# APM32F103RCT6.net
KiCad netlist of a schematic drawn in Altium Designer
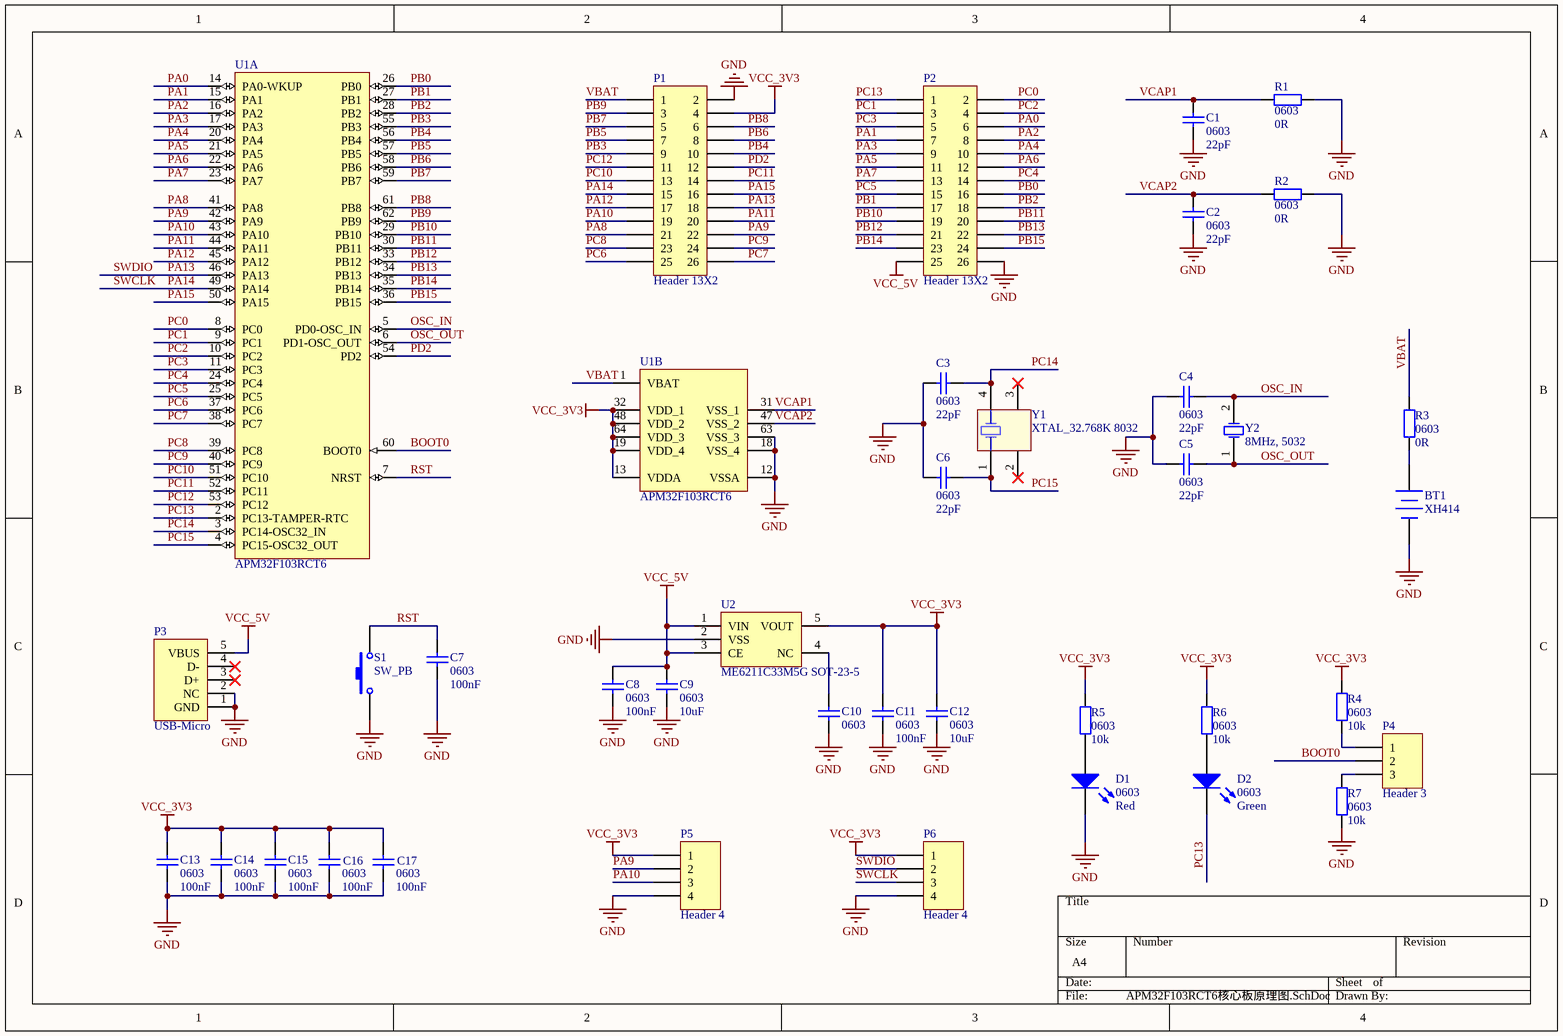
[diagram p0: APM32F103RCT6核心板原理图.SchDoc]

(export (version "E")
  (design (tool "Eeschema 10.0.6"))
  (components
    (comp (ref "BT1")
      (value "XH414")
      (footprint "XH414")
      (description "Multicell Battery")
      (fields (field (name "PUBLISHER") "Altium Limited"))
      (libsource (lib "Miscellaneous Devices") (part "Battery"))
    )
    (comp (ref "C1")
      (value "22pF")
      (footprint "0603")
      (description "Capacitor 0603")
      (fields (field (name "Comment") "Cap 0603"))
      (libsource (lib "Schlib1") (part "Cap 0603"))
    )
    (comp (ref "C2")
      (value "22pF")
      (footprint "0603")
      (description "Capacitor 0603")
      (fields (field (name "Comment") "Cap 0603"))
      (libsource (lib "Schlib1") (part "Cap 0603"))
    )
    (comp (ref "C3")
      (value "22pF")
      (footprint "0603")
      (description "Capacitor 0603")
      (fields (field (name "Comment") "Cap 0603"))
      (libsource (lib "Schlib1") (part "Cap 0603"))
    )
    (comp (ref "C4")
      (value "22pF")
      (footprint "0603")
      (description "Capacitor 0603")
      (fields (field (name "Comment") "Cap 0603"))
      (libsource (lib "Schlib1") (part "Cap 0603"))
    )
    (comp (ref "C5")
      (value "22pF")
      (footprint "0603")
      (description "Capacitor 0603")
      (fields (field (name "Comment") "Cap 0603"))
      (libsource (lib "Schlib1") (part "Cap 0603"))
    )
    (comp (ref "C6")
      (value "22pF")
      (footprint "0603")
      (description "Capacitor 0603")
      (fields (field (name "Comment") "Cap 0603"))
      (libsource (lib "Schlib1") (part "Cap 0603"))
    )
    (comp (ref "C7")
      (value "100nF")
      (footprint "0603")
      (description "Capacitor 0603")
      (fields (field (name "Comment") "Cap 0603"))
      (libsource (lib "Schlib1") (part "Cap 0603"))
    )
    (comp (ref "C8")
      (value "100nF")
      (footprint "0603")
      (description "Capacitor 0603")
      (fields (field (name "Comment") "Cap 0603"))
      (libsource (lib "Schlib1") (part "Cap 0603"))
    )
    (comp (ref "C9")
      (value "10uF")
      (footprint "0603")
      (description "Capacitor 0603")
      (fields (field (name "Comment") "Cap 0603"))
      (libsource (lib "Schlib1") (part "Cap 0603"))
    )
    (comp (ref "C10")
      (value "Cap 0603")
      (footprint "0603")
      (description "Capacitor 0603")
      (libsource (lib "Schlib1") (part "Cap 0603"))
    )
    (comp (ref "C11")
      (value "100nF")
      (footprint "0603")
      (description "Capacitor 0603")
      (fields (field (name "Comment") "Cap 0603"))
      (libsource (lib "Schlib1") (part "Cap 0603"))
    )
    (comp (ref "C12")
      (value "10uF")
      (footprint "0603")
      (description "Capacitor 0603")
      (fields (field (name "Comment") "Cap 0603"))
      (libsource (lib "Schlib1") (part "Cap 0603"))
    )
    (comp (ref "C13")
      (value "100nF")
      (footprint "0603")
      (description "Capacitor 0603")
      (fields (field (name "Comment") "Cap 0603"))
      (libsource (lib "Schlib1") (part "Cap 0603"))
    )
    (comp (ref "C14")
      (value "100nF")
      (footprint "0603")
      (description "Capacitor 0603")
      (fields (field (name "Comment") "Cap 0603"))
      (libsource (lib "Schlib1") (part "Cap 0603"))
    )
    (comp (ref "C15")
      (value "100nF")
      (footprint "0603")
      (description "Capacitor 0603")
      (fields (field (name "Comment") "Cap 0603"))
      (libsource (lib "Schlib1") (part "Cap 0603"))
    )
    (comp (ref "C16")
      (value "100nF")
      (footprint "0603")
      (description "Capacitor 0603")
      (fields (field (name "Comment") "Cap 0603"))
      (libsource (lib "Schlib1") (part "Cap 0603"))
    )
    (comp (ref "C17")
      (value "100nF")
      (footprint "0603")
      (description "Capacitor 0603")
      (fields (field (name "Comment") "Cap 0603"))
      (libsource (lib "Schlib1") (part "Cap 0603"))
    )
    (comp (ref "D1")
      (value "Red")
      (footprint "0603")
      (description "LED 0603")
      (libsource (lib "Schlib1") (part "LED 0603"))
    )
    (comp (ref "D2")
      (value "Green")
      (footprint "0603")
      (description "LED 0603")
      (libsource (lib "Schlib1") (part "LED 0603"))
    )
    (comp (ref "P1")
      (value "Header 13X2")
      (footprint "HDR2X13")
      (description "Header, 13-Pin, Dual row")
      (fields (field (name "PUBLISHER") "Altium Limited"))
      (libsource (lib "Miscellaneous Connectors") (part "Header 13X2"))
    )
    (comp (ref "P2")
      (value "Header 13X2")
      (footprint "HDR2X13")
      (description "Header, 13-Pin, Dual row")
      (fields (field (name "PUBLISHER") "Altium Limited"))
      (libsource (lib "Miscellaneous Connectors") (part "Header 13X2"))
    )
    (comp (ref "P3")
      (value "USB-Micro")
      (footprint "USB Micro")
      (libsource (lib "Schlib1") (part "USB-Micro"))
    )
    (comp (ref "P4")
      (value "Header 3")
      (footprint "HDR1X3")
      (description "Header, 3-Pin")
      (fields (field (name "PUBLISHER") "Altium Limited"))
      (libsource (lib "Miscellaneous Connectors") (part "Header 3"))
    )
    (comp (ref "P5")
      (value "Header 4")
      (footprint "HDR1X4")
      (description "Header, 4-Pin")
      (fields (field (name "PUBLISHER") "Altium Limited"))
      (libsource (lib "Miscellaneous Connectors") (part "Header 4"))
    )
    (comp (ref "P6")
      (value "Header 4")
      (footprint "HDR1X4")
      (description "Header, 4-Pin")
      (fields (field (name "PUBLISHER") "Altium Limited"))
      (libsource (lib "Miscellaneous Connectors") (part "Header 4"))
    )
    (comp (ref "R1")
      (value "0R")
      (footprint "0603")
      (description "Resistor 0603")
      (fields (field (name "Comment") "Res 0603"))
      (libsource (lib "Schlib1") (part "Res 0603"))
    )
    (comp (ref "R2")
      (value "0R")
      (footprint "0603")
      (description "Resistor 0603")
      (fields (field (name "Comment") "Res 0603"))
      (libsource (lib "Schlib1") (part "Res 0603"))
    )
    (comp (ref "R3")
      (value "0R")
      (footprint "0603")
      (description "Resistor 0603")
      (fields (field (name "Comment") "Res 0603"))
      (libsource (lib "") (part "Res 0603_1"))
    )
    (comp (ref "R4")
      (value "10k")
      (footprint "0603")
      (description "Resistor 0603")
      (fields (field (name "Comment") "Res 0603"))
      (libsource (lib "") (part "Res 0603_2"))
    )
    (comp (ref "R5")
      (value "10k")
      (footprint "0603")
      (description "Resistor 0603")
      (fields (field (name "Comment") "Res 0603"))
      (libsource (lib "") (part "Res 0603_1"))
    )
    (comp (ref "R6")
      (value "10k")
      (footprint "0603")
      (description "Resistor 0603")
      (fields (field (name "Comment") "Res 0603"))
      (libsource (lib "") (part "Res 0603_1"))
    )
    (comp (ref "R7")
      (value "10k")
      (footprint "0603")
      (description "Resistor 0603")
      (fields (field (name "Comment") "Res 0603"))
      (libsource (lib "") (part "Res 0603_2"))
    )
    (comp (ref "S1") (value "SW_PB") (footprint "SW-2Pin") (libsource (lib "Schlib1") (part "SW_PB")))
    (comp (ref "U1")
      (value "APM32F103RCT6")
      (footprint "STM-LQFP64_M")
      (fields (field (name "PARTNUMBER") "STM32F103RCT6"))
      (libsource (lib "STMicroelectronics STM32 F1") (part "STM32F103RCT6"))
    )
    (comp (ref "U2")
      (value "ME6211C33M5G SOT-23-5")
      (footprint "SOT-23-5")
      (libsource (lib "Schlib1") (part "ME6211C33M5G"))
    )
    (comp (ref "Y1")
      (value "XTAL_32.768K 8032")
      (footprint "XTAL_8032")
      (libsource (lib "Schlib1") (part "XTAL_32.768K 8032"))
    )
    (comp (ref "Y2")
      (value "8MHz, 5032")
      (footprint "XTAL 5032")
      (description "Crystal Oscillator")
      (fields (field (name "PUBLISHER") "Altium Limited"))
      (libsource (lib "Schlib1") (part "XTAL"))
    )
  )
  (nets
    (net (code "1") (name "/BOOT0") (class "Default")
      (node (ref "P4") (pin "2") (pinfunction "2_2") (pintype "passive"))
      (node (ref "U1") (pin "60") (pinfunction "BOOT0_60") (pintype "input"))
    )
    (net (code "2") (name "/OSC_IN") (class "Default")
      (node (ref "C4") (pin "1") (pinfunction "1_1") (pintype "passive"))
      (node (ref "U1") (pin "5") (pinfunction "PD0-OSC_IN_5") (pintype "bidirectional"))
      (node (ref "Y2") (pin "2") (pinfunction "OSC2_2") (pintype "passive"))
    )
    (net (code "3") (name "/OSC_OUT") (class "Default")
      (node (ref "C5") (pin "1") (pinfunction "1_1") (pintype "passive"))
      (node (ref "U1") (pin "6") (pinfunction "PD1-OSC_OUT_6") (pintype "bidirectional"))
      (node (ref "Y2") (pin "1") (pinfunction "OSC1_1") (pintype "passive"))
    )
    (net (code "4") (name "/PA0") (class "Default")
      (node (ref "P2") (pin "6") (pinfunction "6_6") (pintype "passive"))
      (node (ref "U1") (pin "14") (pinfunction "PA0-WKUP_14") (pintype "bidirectional"))
    )
    (net (code "5") (name "/PA1") (class "Default")
      (node (ref "P2") (pin "7") (pinfunction "7_7") (pintype "passive"))
      (node (ref "U1") (pin "15") (pinfunction "PA1_15") (pintype "bidirectional"))
    )
    (net (code "6") (name "/PA2") (class "Default")
      (node (ref "P2") (pin "8") (pinfunction "8_8") (pintype "passive"))
      (node (ref "U1") (pin "16") (pinfunction "PA2_16") (pintype "bidirectional"))
    )
    (net (code "7") (name "/PA3") (class "Default")
      (node (ref "P2") (pin "9") (pinfunction "9_9") (pintype "passive"))
      (node (ref "U1") (pin "17") (pinfunction "PA3_17") (pintype "bidirectional"))
    )
    (net (code "8") (name "/PA4") (class "Default")
      (node (ref "P2") (pin "10") (pinfunction "10_10") (pintype "passive"))
      (node (ref "U1") (pin "20") (pinfunction "PA4_20") (pintype "bidirectional"))
    )
    (net (code "9") (name "/PA5") (class "Default")
      (node (ref "P2") (pin "11") (pinfunction "11_11") (pintype "passive"))
      (node (ref "U1") (pin "21") (pinfunction "PA5_21") (pintype "bidirectional"))
    )
    (net (code "10") (name "/PA6") (class "Default")
      (node (ref "P2") (pin "12") (pinfunction "12_12") (pintype "passive"))
      (node (ref "U1") (pin "22") (pinfunction "PA6_22") (pintype "bidirectional"))
    )
    (net (code "11") (name "/PA7") (class "Default")
      (node (ref "P2") (pin "13") (pinfunction "13_13") (pintype "passive"))
      (node (ref "U1") (pin "23") (pinfunction "PA7_23") (pintype "bidirectional"))
    )
    (net (code "12") (name "/PA8") (class "Default")
      (node (ref "P1") (pin "21") (pinfunction "21_21") (pintype "passive"))
      (node (ref "U1") (pin "41") (pinfunction "PA8_41") (pintype "bidirectional"))
    )
    (net (code "13") (name "/PA9") (class "Default")
      (node (ref "P1") (pin "22") (pinfunction "22_22") (pintype "passive"))
      (node (ref "P5") (pin "2") (pinfunction "2_2") (pintype "passive"))
      (node (ref "U1") (pin "42") (pinfunction "PA9_42") (pintype "bidirectional"))
    )
    (net (code "14") (name "/PA10") (class "Default")
      (node (ref "P1") (pin "19") (pinfunction "19_19") (pintype "passive"))
      (node (ref "P5") (pin "3") (pinfunction "3_3") (pintype "passive"))
      (node (ref "U1") (pin "43") (pinfunction "PA10_43") (pintype "bidirectional"))
    )
    (net (code "15") (name "/PA11") (class "Default")
      (node (ref "P1") (pin "20") (pinfunction "20_20") (pintype "passive"))
      (node (ref "U1") (pin "44") (pinfunction "PA11_44") (pintype "bidirectional"))
    )
    (net (code "16") (name "/PA12") (class "Default")
      (node (ref "P1") (pin "17") (pinfunction "17_17") (pintype "passive"))
      (node (ref "U1") (pin "45") (pinfunction "PA12_45") (pintype "bidirectional"))
    )
    (net (code "17") (name "/PA13") (class "Default")
      (node (ref "P1") (pin "18") (pinfunction "18_18") (pintype "passive"))
      (node (ref "P6") (pin "2") (pinfunction "2_2") (pintype "passive"))
      (node (ref "U1") (pin "46") (pinfunction "PA13_46") (pintype "bidirectional"))
    )
    (net (code "18") (name "/PA14") (class "Default")
      (node (ref "P1") (pin "15") (pinfunction "15_15") (pintype "passive"))
      (node (ref "P6") (pin "3") (pinfunction "3_3") (pintype "passive"))
      (node (ref "U1") (pin "49") (pinfunction "PA14_49") (pintype "bidirectional"))
    )
    (net (code "19") (name "/PA15") (class "Default")
      (node (ref "P1") (pin "16") (pinfunction "16_16") (pintype "passive"))
      (node (ref "U1") (pin "50") (pinfunction "PA15_50") (pintype "bidirectional"))
    )
    (net (code "20") (name "/PB0") (class "Default")
      (node (ref "P2") (pin "16") (pinfunction "16_16") (pintype "passive"))
      (node (ref "U1") (pin "26") (pinfunction "PB0_26") (pintype "bidirectional"))
    )
    (net (code "21") (name "/PB1") (class "Default")
      (node (ref "P2") (pin "17") (pinfunction "17_17") (pintype "passive"))
      (node (ref "U1") (pin "27") (pinfunction "PB1_27") (pintype "bidirectional"))
    )
    (net (code "22") (name "/PB2") (class "Default")
      (node (ref "P2") (pin "18") (pinfunction "18_18") (pintype "passive"))
      (node (ref "U1") (pin "28") (pinfunction "PB2_28") (pintype "bidirectional"))
    )
    (net (code "23") (name "/PB3") (class "Default")
      (node (ref "P1") (pin "9") (pinfunction "9_9") (pintype "passive"))
      (node (ref "U1") (pin "55") (pinfunction "PB3_55") (pintype "bidirectional"))
    )
    (net (code "24") (name "/PB4") (class "Default")
      (node (ref "P1") (pin "10") (pinfunction "10_10") (pintype "passive"))
      (node (ref "U1") (pin "56") (pinfunction "PB4_56") (pintype "bidirectional"))
    )
    (net (code "25") (name "/PB5") (class "Default")
      (node (ref "P1") (pin "7") (pinfunction "7_7") (pintype "passive"))
      (node (ref "U1") (pin "57") (pinfunction "PB5_57") (pintype "bidirectional"))
    )
    (net (code "26") (name "/PB6") (class "Default")
      (node (ref "P1") (pin "8") (pinfunction "8_8") (pintype "passive"))
      (node (ref "U1") (pin "58") (pinfunction "PB6_58") (pintype "bidirectional"))
    )
    (net (code "27") (name "/PB7") (class "Default")
      (node (ref "P1") (pin "5") (pinfunction "5_5") (pintype "passive"))
      (node (ref "U1") (pin "59") (pinfunction "PB7_59") (pintype "bidirectional"))
    )
    (net (code "28") (name "/PB8") (class "Default")
      (node (ref "P1") (pin "6") (pinfunction "6_6") (pintype "passive"))
      (node (ref "U1") (pin "61") (pinfunction "PB8_61") (pintype "bidirectional"))
    )
    (net (code "29") (name "/PB9") (class "Default")
      (node (ref "P1") (pin "3") (pinfunction "3_3") (pintype "passive"))
      (node (ref "U1") (pin "62") (pinfunction "PB9_62") (pintype "bidirectional"))
    )
    (net (code "30") (name "/PB10") (class "Default")
      (node (ref "P2") (pin "19") (pinfunction "19_19") (pintype "passive"))
      (node (ref "U1") (pin "29") (pinfunction "PB10_29") (pintype "bidirectional"))
    )
    (net (code "31") (name "/PB11") (class "Default")
      (node (ref "P2") (pin "20") (pinfunction "20_20") (pintype "passive"))
      (node (ref "U1") (pin "30") (pinfunction "PB11_30") (pintype "bidirectional"))
    )
    (net (code "32") (name "/PB12") (class "Default")
      (node (ref "P2") (pin "21") (pinfunction "21_21") (pintype "passive"))
      (node (ref "U1") (pin "33") (pinfunction "PB12_33") (pintype "bidirectional"))
    )
    (net (code "33") (name "/PB13") (class "Default")
      (node (ref "P2") (pin "22") (pinfunction "22_22") (pintype "passive"))
      (node (ref "U1") (pin "34") (pinfunction "PB13_34") (pintype "bidirectional"))
    )
    (net (code "34") (name "/PB14") (class "Default")
      (node (ref "P2") (pin "23") (pinfunction "23_23") (pintype "passive"))
      (node (ref "U1") (pin "35") (pinfunction "PB14_35") (pintype "bidirectional"))
    )
    (net (code "35") (name "/PB15") (class "Default")
      (node (ref "P2") (pin "24") (pinfunction "24_24") (pintype "passive"))
      (node (ref "U1") (pin "36") (pinfunction "PB15_36") (pintype "bidirectional"))
    )
    (net (code "36") (name "/PC0") (class "Default")
      (node (ref "P2") (pin "2") (pinfunction "2_2") (pintype "passive"))
      (node (ref "U1") (pin "8") (pinfunction "PC0_8") (pintype "bidirectional"))
    )
    (net (code "37") (name "/PC1") (class "Default")
      (node (ref "P2") (pin "3") (pinfunction "3_3") (pintype "passive"))
      (node (ref "U1") (pin "9") (pinfunction "PC1_9") (pintype "bidirectional"))
    )
    (net (code "38") (name "/PC2") (class "Default")
      (node (ref "P2") (pin "4") (pinfunction "4_4") (pintype "passive"))
      (node (ref "U1") (pin "10") (pinfunction "PC2_10") (pintype "bidirectional"))
    )
    (net (code "39") (name "/PC3") (class "Default")
      (node (ref "P2") (pin "5") (pinfunction "5_5") (pintype "passive"))
      (node (ref "U1") (pin "11") (pinfunction "PC3_11") (pintype "bidirectional"))
    )
    (net (code "40") (name "/PC4") (class "Default")
      (node (ref "P2") (pin "14") (pinfunction "14_14") (pintype "passive"))
      (node (ref "U1") (pin "24") (pinfunction "PC4_24") (pintype "bidirectional"))
    )
    (net (code "41") (name "/PC5") (class "Default")
      (node (ref "P2") (pin "15") (pinfunction "15_15") (pintype "passive"))
      (node (ref "U1") (pin "25") (pinfunction "PC5_25") (pintype "bidirectional"))
    )
    (net (code "42") (name "/PC6") (class "Default")
      (node (ref "P1") (pin "25") (pinfunction "25_25") (pintype "passive"))
      (node (ref "U1") (pin "37") (pinfunction "PC6_37") (pintype "bidirectional"))
    )
    (net (code "43") (name "/PC7") (class "Default")
      (node (ref "P1") (pin "26") (pinfunction "26_26") (pintype "passive"))
      (node (ref "U1") (pin "38") (pinfunction "PC7_38") (pintype "bidirectional"))
    )
    (net (code "44") (name "/PC8") (class "Default")
      (node (ref "P1") (pin "23") (pinfunction "23_23") (pintype "passive"))
      (node (ref "U1") (pin "39") (pinfunction "PC8_39") (pintype "bidirectional"))
    )
    (net (code "45") (name "/PC9") (class "Default")
      (node (ref "P1") (pin "24") (pinfunction "24_24") (pintype "passive"))
      (node (ref "U1") (pin "40") (pinfunction "PC9_40") (pintype "bidirectional"))
    )
    (net (code "46") (name "/PC10") (class "Default")
      (node (ref "P1") (pin "13") (pinfunction "13_13") (pintype "passive"))
      (node (ref "U1") (pin "51") (pinfunction "PC10_51") (pintype "bidirectional"))
    )
    (net (code "47") (name "/PC11") (class "Default")
      (node (ref "P1") (pin "14") (pinfunction "14_14") (pintype "passive"))
      (node (ref "U1") (pin "52") (pinfunction "PC11_52") (pintype "bidirectional"))
    )
    (net (code "48") (name "/PC12") (class "Default")
      (node (ref "P1") (pin "11") (pinfunction "11_11") (pintype "passive"))
      (node (ref "U1") (pin "53") (pinfunction "PC12_53") (pintype "bidirectional"))
    )
    (net (code "49") (name "/PC13") (class "Default")
      (node (ref "D2") (pin "2") (pinfunction "K_2") (pintype "passive"))
      (node (ref "P2") (pin "1") (pinfunction "1_1") (pintype "passive"))
      (node (ref "U1") (pin "2") (pinfunction "PC13-TAMPER-RTC_2") (pintype "bidirectional"))
    )
    (net (code "50") (name "/PC14") (class "Default")
      (node (ref "C3") (pin "1") (pinfunction "1_1") (pintype "passive"))
      (node (ref "U1") (pin "3") (pinfunction "PC14-OSC32_IN_3") (pintype "bidirectional"))
      (node (ref "Y1") (pin "4") (pinfunction "OSC2_4") (pintype "passive"))
    )
    (net (code "51") (name "/PC15") (class "Default")
      (node (ref "C6") (pin "1") (pinfunction "1_1") (pintype "passive"))
      (node (ref "U1") (pin "4") (pinfunction "PC15-OSC32_OUT_4") (pintype "bidirectional"))
      (node (ref "Y1") (pin "1") (pinfunction "OSC1_1") (pintype "passive"))
    )
    (net (code "52") (name "/PD2") (class "Default")
      (node (ref "P1") (pin "12") (pinfunction "12_12") (pintype "passive"))
      (node (ref "U1") (pin "54") (pinfunction "PD2_54") (pintype "bidirectional"))
    )
    (net (code "53") (name "/RST") (class "Default")
      (node (ref "C7") (pin "2") (pinfunction "2_2") (pintype "passive"))
      (node (ref "S1") (pin "2") (pinfunction "2_2") (pintype "passive"))
      (node (ref "U1") (pin "7") (pinfunction "NRST_7") (pintype "bidirectional"))
    )
    (net (code "54") (name "/VBAT") (class "Default")
      (node (ref "P1") (pin "1") (pinfunction "1_1") (pintype "passive"))
      (node (ref "R3") (pin "1") (pinfunction "1_1") (pintype "passive"))
      (node (ref "U1") (pin "1") (pinfunction "VBAT_1") (pintype "power_in"))
    )
    (net (code "55") (name "/VCAP1") (class "Default")
      (node (ref "C1") (pin "1") (pinfunction "1_1") (pintype "passive"))
      (node (ref "R1") (pin "1") (pinfunction "1_1") (pintype "passive"))
      (node (ref "U1") (pin "31") (pinfunction "VSS_1_31") (pintype "power_in"))
    )
    (net (code "56") (name "/VCAP2") (class "Default")
      (node (ref "C2") (pin "1") (pinfunction "1_1") (pintype "passive"))
      (node (ref "R2") (pin "1") (pinfunction "1_1") (pintype "passive"))
      (node (ref "U1") (pin "47") (pinfunction "VSS_2_47") (pintype "power_in"))
    )
    (net (code "57") (name "GND") (class "Default")
      (node (ref "BT1") (pin "2") (pinfunction "-_2") (pintype "passive"))
      (node (ref "C1") (pin "2") (pinfunction "2_2") (pintype "passive"))
      (node (ref "C10") (pin "1") (pinfunction "1_1") (pintype "passive"))
      (node (ref "C11") (pin "1") (pinfunction "1_1") (pintype "passive"))
      (node (ref "C12") (pin "1") (pinfunction "1_1") (pintype "passive"))
      (node (ref "C13") (pin "1") (pinfunction "1_1") (pintype "passive"))
      (node (ref "C14") (pin "1") (pinfunction "1_1") (pintype "passive"))
      (node (ref "C15") (pin "1") (pinfunction "1_1") (pintype "passive"))
      (node (ref "C16") (pin "1") (pinfunction "1_1") (pintype "passive"))
      (node (ref "C17") (pin "1") (pinfunction "1_1") (pintype "passive"))
      (node (ref "C2") (pin "2") (pinfunction "2_2") (pintype "passive"))
      (node (ref "C3") (pin "2") (pinfunction "2_2") (pintype "passive"))
      (node (ref "C4") (pin "2") (pinfunction "2_2") (pintype "passive"))
      (node (ref "C5") (pin "2") (pinfunction "2_2") (pintype "passive"))
      (node (ref "C6") (pin "2") (pinfunction "2_2") (pintype "passive"))
      (node (ref "C7") (pin "1") (pinfunction "1_1") (pintype "passive"))
      (node (ref "C8") (pin "1") (pinfunction "1_1") (pintype "passive"))
      (node (ref "C9") (pin "1") (pinfunction "1_1") (pintype "passive"))
      (node (ref "D1") (pin "2") (pinfunction "K_2") (pintype "passive"))
      (node (ref "P1") (pin "2") (pinfunction "2_2") (pintype "passive"))
      (node (ref "P2") (pin "26") (pinfunction "26_26") (pintype "passive"))
      (node (ref "P3") (pin "1") (pinfunction "GND_1") (pintype "power_in"))
      (node (ref "P3") (pin "2") (pinfunction "NC_2") (pintype "power_in"))
      (node (ref "P5") (pin "4") (pinfunction "4_4") (pintype "passive"))
      (node (ref "P6") (pin "4") (pinfunction "4_4") (pintype "passive"))
      (node (ref "R1") (pin "2") (pinfunction "2_2") (pintype "passive"))
      (node (ref "R2") (pin "2") (pinfunction "2_2") (pintype "passive"))
      (node (ref "R7") (pin "1") (pinfunction "1_1") (pintype "passive"))
      (node (ref "S1") (pin "1") (pinfunction "1_1") (pintype "passive"))
      (node (ref "U1") (pin "12") (pinfunction "VSSA_12") (pintype "power_in"))
      (node (ref "U1") (pin "18") (pinfunction "VSS_4_18") (pintype "power_in"))
      (node (ref "U1") (pin "63") (pinfunction "VSS_3_63") (pintype "power_in"))
      (node (ref "U2") (pin "2") (pinfunction "VSS_2") (pintype "power_in"))
    )
    (net (code "58") (name "Net-(BT1-+)") (class "Default")
      (node (ref "BT1") (pin "1") (pinfunction "+_1") (pintype "passive"))
      (node (ref "R3") (pin "2") (pinfunction "2_2") (pintype "passive"))
    )
    (net (code "59") (name "Net-(D1-A)") (class "Default")
      (node (ref "D1") (pin "1") (pinfunction "A_1") (pintype "passive"))
      (node (ref "R5") (pin "2") (pinfunction "2_2") (pintype "passive"))
    )
    (net (code "60") (name "Net-(D2-A)") (class "Default")
      (node (ref "D2") (pin "1") (pinfunction "A_1") (pintype "passive"))
      (node (ref "R6") (pin "2") (pinfunction "2_2") (pintype "passive"))
    )
    (net (code "61") (name "Net-(P4-Pad1)") (class "Default")
      (node (ref "P4") (pin "1") (pinfunction "1_1") (pintype "passive"))
      (node (ref "R4") (pin "1") (pinfunction "1_1") (pintype "passive"))
    )
    (net (code "62") (name "Net-(P4-Pad3)") (class "Default")
      (node (ref "P4") (pin "3") (pinfunction "3_3") (pintype "passive"))
      (node (ref "R7") (pin "2") (pinfunction "2_2") (pintype "passive"))
    )
    (net (code "63") (name "Net-(U2-NC)") (class "Default")
      (node (ref "C10") (pin "2") (pinfunction "2_2") (pintype "passive"))
      (node (ref "U2") (pin "4") (pinfunction "NC_4") (pintype "power_in"))
    )
    (net (code "64") (name "VCC_3V3") (class "Default")
      (node (ref "C11") (pin "2") (pinfunction "2_2") (pintype "passive"))
      (node (ref "C12") (pin "2") (pinfunction "2_2") (pintype "passive"))
      (node (ref "C13") (pin "2") (pinfunction "2_2") (pintype "passive"))
      (node (ref "C14") (pin "2") (pinfunction "2_2") (pintype "passive"))
      (node (ref "C15") (pin "2") (pinfunction "2_2") (pintype "passive"))
      (node (ref "C16") (pin "2") (pinfunction "2_2") (pintype "passive"))
      (node (ref "C17") (pin "2") (pinfunction "2_2") (pintype "passive"))
      (node (ref "P1") (pin "4") (pinfunction "4_4") (pintype "passive"))
      (node (ref "P5") (pin "1") (pinfunction "1_1") (pintype "passive"))
      (node (ref "P6") (pin "1") (pinfunction "1_1") (pintype "passive"))
      (node (ref "R4") (pin "2") (pinfunction "2_2") (pintype "passive"))
      (node (ref "R5") (pin "1") (pinfunction "1_1") (pintype "passive"))
      (node (ref "R6") (pin "1") (pinfunction "1_1") (pintype "passive"))
      (node (ref "U1") (pin "13") (pinfunction "VDDA_13") (pintype "power_in"))
      (node (ref "U1") (pin "19") (pinfunction "VDD_4_19") (pintype "power_in"))
      (node (ref "U1") (pin "32") (pinfunction "VDD_1_32") (pintype "power_in"))
      (node (ref "U1") (pin "48") (pinfunction "VDD_2_48") (pintype "power_in"))
      (node (ref "U1") (pin "64") (pinfunction "VDD_3_64") (pintype "power_in"))
      (node (ref "U2") (pin "5") (pinfunction "VOUT_5") (pintype "power_in"))
    )
    (net (code "65") (name "VCC_5V") (class "Default")
      (node (ref "C8") (pin "2") (pinfunction "2_2") (pintype "passive"))
      (node (ref "C9") (pin "2") (pinfunction "2_2") (pintype "passive"))
      (node (ref "P2") (pin "25") (pinfunction "25_25") (pintype "passive"))
      (node (ref "P3") (pin "5") (pinfunction "VBUS_5") (pintype "power_in"))
      (node (ref "U2") (pin "1") (pinfunction "VIN_1") (pintype "power_in"))
      (node (ref "U2") (pin "3") (pinfunction "CE_3") (pintype "power_in"))
    )
    (net (code "66") (name "unconnected-(P3-D+-Pad3)") (class "Default")
      (node (ref "P3") (pin "3") (pinfunction "D+_3") (pintype "power_in+no_connect"))
    )
    (net (code "67") (name "unconnected-(P3-D--Pad4)") (class "Default")
      (node (ref "P3") (pin "4") (pinfunction "D-_4") (pintype "power_in+no_connect"))
    )
    (net (code "68") (name "unconnected-(Y1-NC-Pad2)") (class "Default")
      (node (ref "Y1") (pin "2") (pinfunction "NC_2") (pintype "power_in+no_connect"))
    )
    (net (code "69") (name "unconnected-(Y1-NC-Pad3)") (class "Default")
      (node (ref "Y1") (pin "3") (pinfunction "NC_3") (pintype "power_in+no_connect"))
    )
  )
)
